# sensor.net
KiCad netlist of a schematic drawn in Altium Designer
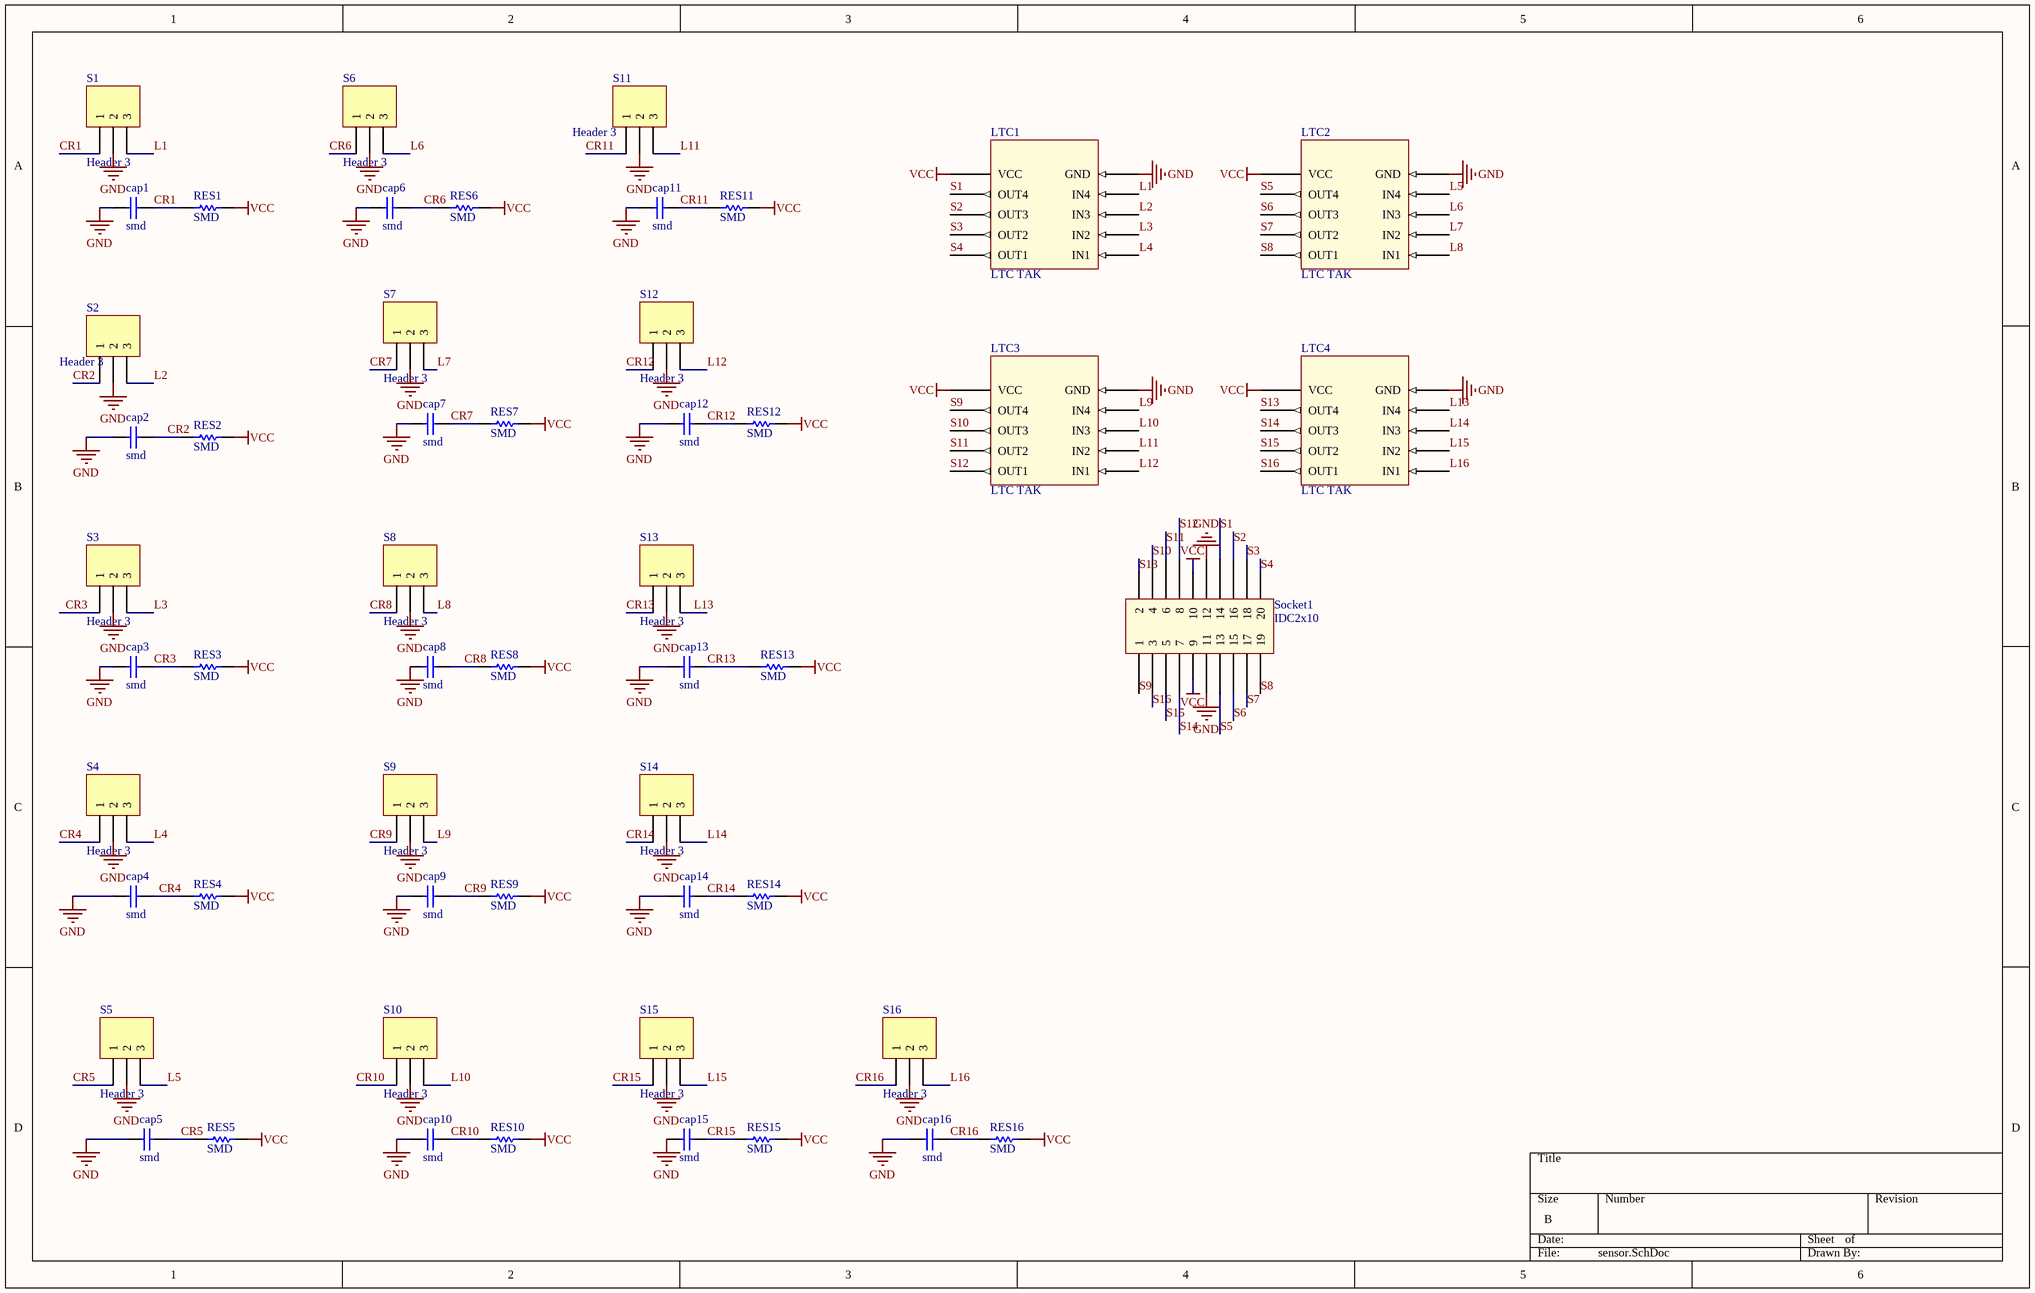
[diagram p0: sensor.SchDoc]

(export (version "E")
  (design (tool "Eeschema 10.0.6"))
  (components
    (comp (ref "cap1") (value "smd") (footprint "Cap SMD") (libsource (lib "Farzanegan") (part "Cap SMD")))
    (comp (ref "cap2") (value "smd") (footprint "Cap SMD") (libsource (lib "Farzanegan") (part "Cap SMD")))
    (comp (ref "cap3") (value "smd") (footprint "Cap SMD") (libsource (lib "Farzanegan") (part "Cap SMD")))
    (comp (ref "cap4") (value "smd") (footprint "Cap SMD") (libsource (lib "Farzanegan") (part "Cap SMD")))
    (comp (ref "cap5") (value "smd") (footprint "Cap SMD") (libsource (lib "Farzanegan") (part "Cap SMD")))
    (comp (ref "cap6") (value "smd") (footprint "Cap SMD") (libsource (lib "Farzanegan") (part "Cap SMD")))
    (comp (ref "cap7") (value "smd") (footprint "Cap SMD") (libsource (lib "Farzanegan") (part "Cap SMD")))
    (comp (ref "cap8") (value "smd") (footprint "Cap SMD") (libsource (lib "Farzanegan") (part "Cap SMD")))
    (comp (ref "cap9") (value "smd") (footprint "Cap SMD") (libsource (lib "Farzanegan") (part "Cap SMD")))
    (comp (ref "cap10") (value "smd") (footprint "Cap SMD") (libsource (lib "Farzanegan") (part "Cap SMD")))
    (comp (ref "cap11") (value "smd") (footprint "Cap SMD") (libsource (lib "Farzanegan") (part "Cap SMD")))
    (comp (ref "cap12") (value "smd") (footprint "Cap SMD") (libsource (lib "Farzanegan") (part "Cap SMD")))
    (comp (ref "cap13") (value "smd") (footprint "Cap SMD") (libsource (lib "Farzanegan") (part "Cap SMD")))
    (comp (ref "cap14") (value "smd") (footprint "Cap SMD") (libsource (lib "Farzanegan") (part "Cap SMD")))
    (comp (ref "cap15") (value "smd") (footprint "Cap SMD") (libsource (lib "Farzanegan") (part "Cap SMD")))
    (comp (ref "cap16") (value "smd") (footprint "Cap SMD") (libsource (lib "Farzanegan") (part "Cap SMD")))
    (comp (ref "LTC1")
      (value "LTC TAK")
      (footprint "LTC TAK")
      (libsource (lib "Farzanegan") (part "LTC TAK"))
    )
    (comp (ref "LTC2")
      (value "LTC TAK")
      (footprint "LTC TAK")
      (libsource (lib "Farzanegan") (part "LTC TAK"))
    )
    (comp (ref "LTC3")
      (value "LTC TAK")
      (footprint "LTC TAK")
      (libsource (lib "Farzanegan") (part "LTC TAK"))
    )
    (comp (ref "LTC4")
      (value "LTC TAK")
      (footprint "LTC TAK")
      (libsource (lib "Farzanegan") (part "LTC TAK"))
    )
    (comp (ref "RES1")
      (value "SMD")
      (footprint "Resistor SMD 1206")
      (libsource (lib "Farzanegan") (part "Res SMD"))
    )
    (comp (ref "RES2")
      (value "SMD")
      (footprint "Resistor SMD 1206")
      (libsource (lib "Farzanegan") (part "Res SMD"))
    )
    (comp (ref "RES3")
      (value "SMD")
      (footprint "Resistor SMD 1206")
      (libsource (lib "Farzanegan") (part "Res SMD"))
    )
    (comp (ref "RES4")
      (value "SMD")
      (footprint "Resistor SMD 1206")
      (libsource (lib "Farzanegan") (part "Res SMD"))
    )
    (comp (ref "RES5")
      (value "SMD")
      (footprint "Resistor SMD 1206")
      (libsource (lib "Farzanegan") (part "Res SMD"))
    )
    (comp (ref "RES6")
      (value "SMD")
      (footprint "Resistor SMD 1206")
      (libsource (lib "Farzanegan") (part "Res SMD"))
    )
    (comp (ref "RES7")
      (value "SMD")
      (footprint "Resistor SMD 1206")
      (libsource (lib "Farzanegan") (part "Res SMD"))
    )
    (comp (ref "RES8")
      (value "SMD")
      (footprint "Resistor SMD 1206")
      (libsource (lib "Farzanegan") (part "Res SMD"))
    )
    (comp (ref "RES9")
      (value "SMD")
      (footprint "Resistor SMD 1206")
      (libsource (lib "Farzanegan") (part "Res SMD"))
    )
    (comp (ref "RES10")
      (value "SMD")
      (footprint "Resistor SMD 1206")
      (libsource (lib "Farzanegan") (part "Res SMD"))
    )
    (comp (ref "RES11")
      (value "SMD")
      (footprint "Resistor SMD 1206")
      (libsource (lib "Farzanegan") (part "Res SMD"))
    )
    (comp (ref "RES12")
      (value "SMD")
      (footprint "Resistor SMD 1206")
      (libsource (lib "Farzanegan") (part "Res SMD"))
    )
    (comp (ref "RES13")
      (value "SMD")
      (footprint "Resistor SMD 1206")
      (libsource (lib "Farzanegan") (part "Res SMD"))
    )
    (comp (ref "RES14")
      (value "SMD")
      (footprint "Resistor SMD 1206")
      (libsource (lib "Farzanegan") (part "Res SMD"))
    )
    (comp (ref "RES15")
      (value "SMD")
      (footprint "Resistor SMD 1206")
      (libsource (lib "Farzanegan") (part "Res SMD"))
    )
    (comp (ref "RES16")
      (value "SMD")
      (footprint "Resistor SMD 1206")
      (libsource (lib "Farzanegan") (part "Res SMD"))
    )
    (comp (ref "S1")
      (value "Header 3")
      (footprint "HDR1X3")
      (description "Header, 3-Pin")
      (fields (field (name "PUBLISHER") "Altium Limited"))
      (libsource (lib "Miscellaneous Connectors") (part "Header 3"))
    )
    (comp (ref "S2")
      (value "Header 3")
      (footprint "HDR1X3")
      (description "Header, 3-Pin")
      (fields (field (name "PUBLISHER") "Altium Limited"))
      (libsource (lib "Miscellaneous Connectors") (part "Header 3"))
    )
    (comp (ref "S3")
      (value "Header 3")
      (footprint "HDR1X3")
      (description "Header, 3-Pin")
      (fields (field (name "PUBLISHER") "Altium Limited"))
      (libsource (lib "Miscellaneous Connectors") (part "Header 3"))
    )
    (comp (ref "S4")
      (value "Header 3")
      (footprint "HDR1X3")
      (description "Header, 3-Pin")
      (fields (field (name "PUBLISHER") "Altium Limited"))
      (libsource (lib "Miscellaneous Connectors") (part "Header 3"))
    )
    (comp (ref "S5")
      (value "Header 3")
      (footprint "HDR1X3")
      (description "Header, 3-Pin")
      (fields (field (name "PUBLISHER") "Altium Limited"))
      (libsource (lib "Miscellaneous Connectors") (part "Header 3"))
    )
    (comp (ref "S6")
      (value "Header 3")
      (footprint "HDR1X3")
      (description "Header, 3-Pin")
      (fields (field (name "PUBLISHER") "Altium Limited"))
      (libsource (lib "Miscellaneous Connectors") (part "Header 3"))
    )
    (comp (ref "S7")
      (value "Header 3")
      (footprint "HDR1X3")
      (description "Header, 3-Pin")
      (fields (field (name "PUBLISHER") "Altium Limited"))
      (libsource (lib "Miscellaneous Connectors") (part "Header 3"))
    )
    (comp (ref "S8")
      (value "Header 3")
      (footprint "HDR1X3")
      (description "Header, 3-Pin")
      (fields (field (name "PUBLISHER") "Altium Limited"))
      (libsource (lib "Miscellaneous Connectors") (part "Header 3"))
    )
    (comp (ref "S9")
      (value "Header 3")
      (footprint "HDR1X3")
      (description "Header, 3-Pin")
      (fields (field (name "PUBLISHER") "Altium Limited"))
      (libsource (lib "Miscellaneous Connectors") (part "Header 3"))
    )
    (comp (ref "S10")
      (value "Header 3")
      (footprint "HDR1X3")
      (description "Header, 3-Pin")
      (fields (field (name "PUBLISHER") "Altium Limited"))
      (libsource (lib "Miscellaneous Connectors") (part "Header 3"))
    )
    (comp (ref "S11")
      (value "Header 3")
      (footprint "HDR1X3")
      (description "Header, 3-Pin")
      (fields (field (name "PUBLISHER") "Altium Limited"))
      (libsource (lib "Miscellaneous Connectors") (part "Header 3"))
    )
    (comp (ref "S12")
      (value "Header 3")
      (footprint "HDR1X3")
      (description "Header, 3-Pin")
      (fields (field (name "PUBLISHER") "Altium Limited"))
      (libsource (lib "Miscellaneous Connectors") (part "Header 3"))
    )
    (comp (ref "S13")
      (value "Header 3")
      (footprint "HDR1X3")
      (description "Header, 3-Pin")
      (fields (field (name "PUBLISHER") "Altium Limited"))
      (libsource (lib "Miscellaneous Connectors") (part "Header 3"))
    )
    (comp (ref "S14")
      (value "Header 3")
      (footprint "HDR1X3")
      (description "Header, 3-Pin")
      (fields (field (name "PUBLISHER") "Altium Limited"))
      (libsource (lib "Miscellaneous Connectors") (part "Header 3"))
    )
    (comp (ref "S15")
      (value "Header 3")
      (footprint "HDR1X3")
      (description "Header, 3-Pin")
      (fields (field (name "PUBLISHER") "Altium Limited"))
      (libsource (lib "Miscellaneous Connectors") (part "Header 3"))
    )
    (comp (ref "S16")
      (value "Header 3")
      (footprint "HDR1X3")
      (description "Header, 3-Pin")
      (fields (field (name "PUBLISHER") "Altium Limited"))
      (libsource (lib "Miscellaneous Connectors") (part "Header 3"))
    )
    (comp (ref "Socket1")
      (value "IDC2x10")
      (footprint "IDC 2x10")
      (libsource (lib "Farzanegan") (part "IDC 2x10"))
    )
  )
  (nets
    (net (code "1") (name "/CR1") (class "Default")
      (node (ref "RES1") (pin "1") (pinfunction "1_1") (pintype "passive"))
      (node (ref "S1") (pin "1") (pinfunction "1_1") (pintype "passive"))
      (node (ref "cap1") (pin "2") (pinfunction "2_2") (pintype "passive"))
    )
    (net (code "2") (name "/CR2") (class "Default")
      (node (ref "RES2") (pin "1") (pinfunction "1_1") (pintype "passive"))
      (node (ref "S2") (pin "1") (pinfunction "1_1") (pintype "passive"))
      (node (ref "cap2") (pin "2") (pinfunction "2_2") (pintype "passive"))
    )
    (net (code "3") (name "/CR3") (class "Default")
      (node (ref "RES3") (pin "1") (pinfunction "1_1") (pintype "passive"))
      (node (ref "S3") (pin "1") (pinfunction "1_1") (pintype "passive"))
      (node (ref "cap3") (pin "2") (pinfunction "2_2") (pintype "passive"))
    )
    (net (code "4") (name "/CR4") (class "Default")
      (node (ref "RES4") (pin "1") (pinfunction "1_1") (pintype "passive"))
      (node (ref "S4") (pin "1") (pinfunction "1_1") (pintype "passive"))
      (node (ref "cap4") (pin "2") (pinfunction "2_2") (pintype "passive"))
    )
    (net (code "5") (name "/CR5") (class "Default")
      (node (ref "RES5") (pin "1") (pinfunction "1_1") (pintype "passive"))
      (node (ref "S5") (pin "1") (pinfunction "1_1") (pintype "passive"))
      (node (ref "cap5") (pin "2") (pinfunction "2_2") (pintype "passive"))
    )
    (net (code "6") (name "/CR6") (class "Default")
      (node (ref "RES6") (pin "1") (pinfunction "1_1") (pintype "passive"))
      (node (ref "S6") (pin "1") (pinfunction "1_1") (pintype "passive"))
      (node (ref "cap6") (pin "2") (pinfunction "2_2") (pintype "passive"))
    )
    (net (code "7") (name "/CR7") (class "Default")
      (node (ref "RES7") (pin "1") (pinfunction "1_1") (pintype "passive"))
      (node (ref "S7") (pin "1") (pinfunction "1_1") (pintype "passive"))
      (node (ref "cap7") (pin "2") (pinfunction "2_2") (pintype "passive"))
    )
    (net (code "8") (name "/CR8") (class "Default")
      (node (ref "RES8") (pin "1") (pinfunction "1_1") (pintype "passive"))
      (node (ref "S8") (pin "1") (pinfunction "1_1") (pintype "passive"))
      (node (ref "cap8") (pin "2") (pinfunction "2_2") (pintype "passive"))
    )
    (net (code "9") (name "/CR9") (class "Default")
      (node (ref "RES9") (pin "1") (pinfunction "1_1") (pintype "passive"))
      (node (ref "S9") (pin "1") (pinfunction "1_1") (pintype "passive"))
      (node (ref "cap9") (pin "2") (pinfunction "2_2") (pintype "passive"))
    )
    (net (code "10") (name "/CR10") (class "Default")
      (node (ref "RES10") (pin "1") (pinfunction "1_1") (pintype "passive"))
      (node (ref "S10") (pin "1") (pinfunction "1_1") (pintype "passive"))
      (node (ref "cap10") (pin "2") (pinfunction "2_2") (pintype "passive"))
    )
    (net (code "11") (name "/CR11") (class "Default")
      (node (ref "RES11") (pin "1") (pinfunction "1_1") (pintype "passive"))
      (node (ref "S11") (pin "1") (pinfunction "1_1") (pintype "passive"))
      (node (ref "cap11") (pin "2") (pinfunction "2_2") (pintype "passive"))
    )
    (net (code "12") (name "/CR12") (class "Default")
      (node (ref "RES12") (pin "1") (pinfunction "1_1") (pintype "passive"))
      (node (ref "S12") (pin "1") (pinfunction "1_1") (pintype "passive"))
      (node (ref "cap12") (pin "2") (pinfunction "2_2") (pintype "passive"))
    )
    (net (code "13") (name "/CR13") (class "Default")
      (node (ref "RES13") (pin "1") (pinfunction "1_1") (pintype "passive"))
      (node (ref "S13") (pin "1") (pinfunction "1_1") (pintype "passive"))
      (node (ref "cap13") (pin "2") (pinfunction "2_2") (pintype "passive"))
    )
    (net (code "14") (name "/CR14") (class "Default")
      (node (ref "RES14") (pin "1") (pinfunction "1_1") (pintype "passive"))
      (node (ref "S14") (pin "1") (pinfunction "1_1") (pintype "passive"))
      (node (ref "cap14") (pin "2") (pinfunction "2_2") (pintype "passive"))
    )
    (net (code "15") (name "/CR15") (class "Default")
      (node (ref "RES15") (pin "1") (pinfunction "1_1") (pintype "passive"))
      (node (ref "S15") (pin "1") (pinfunction "1_1") (pintype "passive"))
      (node (ref "cap15") (pin "2") (pinfunction "2_2") (pintype "passive"))
    )
    (net (code "16") (name "/CR16") (class "Default")
      (node (ref "RES16") (pin "1") (pinfunction "1_1") (pintype "passive"))
      (node (ref "S16") (pin "1") (pinfunction "1_1") (pintype "passive"))
      (node (ref "cap16") (pin "2") (pinfunction "2_2") (pintype "passive"))
    )
    (net (code "17") (name "/L1") (class "Default")
      (node (ref "LTC1") (pin "9") (pinfunction "IN4_9") (pintype "input"))
      (node (ref "S1") (pin "3") (pinfunction "3_3") (pintype "passive"))
    )
    (net (code "18") (name "/L2") (class "Default")
      (node (ref "LTC1") (pin "8") (pinfunction "IN3_8") (pintype "input"))
      (node (ref "S2") (pin "3") (pinfunction "3_3") (pintype "passive"))
    )
    (net (code "19") (name "/L3") (class "Default")
      (node (ref "LTC1") (pin "7") (pinfunction "IN2_7") (pintype "input"))
      (node (ref "S3") (pin "3") (pinfunction "3_3") (pintype "passive"))
    )
    (net (code "20") (name "/L4") (class "Default")
      (node (ref "LTC1") (pin "6") (pinfunction "IN1_6") (pintype "input"))
      (node (ref "S4") (pin "3") (pinfunction "3_3") (pintype "passive"))
    )
    (net (code "21") (name "/L5") (class "Default")
      (node (ref "LTC2") (pin "9") (pinfunction "IN4_9") (pintype "input"))
      (node (ref "S5") (pin "3") (pinfunction "3_3") (pintype "passive"))
    )
    (net (code "22") (name "/L6") (class "Default")
      (node (ref "LTC2") (pin "8") (pinfunction "IN3_8") (pintype "input"))
      (node (ref "S6") (pin "3") (pinfunction "3_3") (pintype "passive"))
    )
    (net (code "23") (name "/L7") (class "Default")
      (node (ref "LTC2") (pin "7") (pinfunction "IN2_7") (pintype "input"))
      (node (ref "S7") (pin "3") (pinfunction "3_3") (pintype "passive"))
    )
    (net (code "24") (name "/L8") (class "Default")
      (node (ref "LTC2") (pin "6") (pinfunction "IN1_6") (pintype "input"))
      (node (ref "S8") (pin "3") (pinfunction "3_3") (pintype "passive"))
    )
    (net (code "25") (name "/L9") (class "Default")
      (node (ref "LTC3") (pin "9") (pinfunction "IN4_9") (pintype "input"))
      (node (ref "S9") (pin "3") (pinfunction "3_3") (pintype "passive"))
    )
    (net (code "26") (name "/L10") (class "Default")
      (node (ref "LTC3") (pin "8") (pinfunction "IN3_8") (pintype "input"))
      (node (ref "S10") (pin "3") (pinfunction "3_3") (pintype "passive"))
    )
    (net (code "27") (name "/L11") (class "Default")
      (node (ref "LTC3") (pin "7") (pinfunction "IN2_7") (pintype "input"))
      (node (ref "S11") (pin "3") (pinfunction "3_3") (pintype "passive"))
    )
    (net (code "28") (name "/L12") (class "Default")
      (node (ref "LTC3") (pin "6") (pinfunction "IN1_6") (pintype "input"))
      (node (ref "S12") (pin "3") (pinfunction "3_3") (pintype "passive"))
    )
    (net (code "29") (name "/L13") (class "Default")
      (node (ref "LTC4") (pin "9") (pinfunction "IN4_9") (pintype "input"))
      (node (ref "S13") (pin "3") (pinfunction "3_3") (pintype "passive"))
    )
    (net (code "30") (name "/L14") (class "Default")
      (node (ref "LTC4") (pin "8") (pinfunction "IN3_8") (pintype "input"))
      (node (ref "S14") (pin "3") (pinfunction "3_3") (pintype "passive"))
    )
    (net (code "31") (name "/L15") (class "Default")
      (node (ref "LTC4") (pin "7") (pinfunction "IN2_7") (pintype "input"))
      (node (ref "S15") (pin "3") (pinfunction "3_3") (pintype "passive"))
    )
    (net (code "32") (name "/L16") (class "Default")
      (node (ref "LTC4") (pin "6") (pinfunction "IN1_6") (pintype "input"))
      (node (ref "S16") (pin "3") (pinfunction "3_3") (pintype "passive"))
    )
    (net (code "33") (name "/S1") (class "Default")
      (node (ref "LTC1") (pin "2") (pinfunction "OUT4_2") (pintype "output"))
      (node (ref "Socket1") (pin "14") (pinfunction "14_14") (pintype "passive"))
    )
    (net (code "34") (name "/S2") (class "Default")
      (node (ref "LTC1") (pin "3") (pinfunction "OUT3_3") (pintype "output"))
      (node (ref "Socket1") (pin "16") (pinfunction "16_16") (pintype "passive"))
    )
    (net (code "35") (name "/S3") (class "Default")
      (node (ref "LTC1") (pin "4") (pinfunction "OUT2_4") (pintype "output"))
      (node (ref "Socket1") (pin "18") (pinfunction "18_18") (pintype "passive"))
    )
    (net (code "36") (name "/S4") (class "Default")
      (node (ref "LTC1") (pin "5") (pinfunction "OUT1_5") (pintype "output"))
      (node (ref "Socket1") (pin "20") (pinfunction "20_20") (pintype "passive"))
    )
    (net (code "37") (name "/S5") (class "Default")
      (node (ref "LTC2") (pin "2") (pinfunction "OUT4_2") (pintype "output"))
      (node (ref "Socket1") (pin "13") (pinfunction "13_13") (pintype "passive"))
    )
    (net (code "38") (name "/S6") (class "Default")
      (node (ref "LTC2") (pin "3") (pinfunction "OUT3_3") (pintype "output"))
      (node (ref "Socket1") (pin "15") (pinfunction "15_15") (pintype "passive"))
    )
    (net (code "39") (name "/S7") (class "Default")
      (node (ref "LTC2") (pin "4") (pinfunction "OUT2_4") (pintype "output"))
      (node (ref "Socket1") (pin "17") (pinfunction "17_17") (pintype "passive"))
    )
    (net (code "40") (name "/S8") (class "Default")
      (node (ref "LTC2") (pin "5") (pinfunction "OUT1_5") (pintype "output"))
      (node (ref "Socket1") (pin "19") (pinfunction "19_19") (pintype "passive"))
    )
    (net (code "41") (name "/S9") (class "Default")
      (node (ref "LTC3") (pin "2") (pinfunction "OUT4_2") (pintype "output"))
      (node (ref "Socket1") (pin "1") (pinfunction "1_1") (pintype "passive"))
    )
    (net (code "42") (name "/S10") (class "Default")
      (node (ref "LTC3") (pin "3") (pinfunction "OUT3_3") (pintype "output"))
      (node (ref "Socket1") (pin "4") (pinfunction "4_4") (pintype "passive"))
    )
    (net (code "43") (name "/S11") (class "Default")
      (node (ref "LTC3") (pin "4") (pinfunction "OUT2_4") (pintype "output"))
      (node (ref "Socket1") (pin "6") (pinfunction "6_6") (pintype "passive"))
    )
    (net (code "44") (name "/S12") (class "Default")
      (node (ref "LTC3") (pin "5") (pinfunction "OUT1_5") (pintype "output"))
      (node (ref "Socket1") (pin "8") (pinfunction "8_8") (pintype "passive"))
    )
    (net (code "45") (name "/S13") (class "Default")
      (node (ref "LTC4") (pin "2") (pinfunction "OUT4_2") (pintype "output"))
      (node (ref "Socket1") (pin "2") (pinfunction "2_2") (pintype "passive"))
    )
    (net (code "46") (name "/S14") (class "Default")
      (node (ref "LTC4") (pin "3") (pinfunction "OUT3_3") (pintype "output"))
      (node (ref "Socket1") (pin "7") (pinfunction "7_7") (pintype "passive"))
    )
    (net (code "47") (name "/S15") (class "Default")
      (node (ref "LTC4") (pin "4") (pinfunction "OUT2_4") (pintype "output"))
      (node (ref "Socket1") (pin "5") (pinfunction "5_5") (pintype "passive"))
    )
    (net (code "48") (name "/S16") (class "Default")
      (node (ref "LTC4") (pin "5") (pinfunction "OUT1_5") (pintype "output"))
      (node (ref "Socket1") (pin "3") (pinfunction "3_3") (pintype "passive"))
    )
    (net (code "49") (name "GND") (class "Default")
      (node (ref "LTC1") (pin "10") (pinfunction "GND_10") (pintype "input"))
      (node (ref "LTC2") (pin "10") (pinfunction "GND_10") (pintype "input"))
      (node (ref "LTC3") (pin "10") (pinfunction "GND_10") (pintype "input"))
      (node (ref "LTC4") (pin "10") (pinfunction "GND_10") (pintype "input"))
      (node (ref "S1") (pin "2") (pinfunction "2_2") (pintype "passive"))
      (node (ref "S10") (pin "2") (pinfunction "2_2") (pintype "passive"))
      (node (ref "S11") (pin "2") (pinfunction "2_2") (pintype "passive"))
      (node (ref "S12") (pin "2") (pinfunction "2_2") (pintype "passive"))
      (node (ref "S13") (pin "2") (pinfunction "2_2") (pintype "passive"))
      (node (ref "S14") (pin "2") (pinfunction "2_2") (pintype "passive"))
      (node (ref "S15") (pin "2") (pinfunction "2_2") (pintype "passive"))
      (node (ref "S16") (pin "2") (pinfunction "2_2") (pintype "passive"))
      (node (ref "S2") (pin "2") (pinfunction "2_2") (pintype "passive"))
      (node (ref "S3") (pin "2") (pinfunction "2_2") (pintype "passive"))
      (node (ref "S4") (pin "2") (pinfunction "2_2") (pintype "passive"))
      (node (ref "S5") (pin "2") (pinfunction "2_2") (pintype "passive"))
      (node (ref "S6") (pin "2") (pinfunction "2_2") (pintype "passive"))
      (node (ref "S7") (pin "2") (pinfunction "2_2") (pintype "passive"))
      (node (ref "S8") (pin "2") (pinfunction "2_2") (pintype "passive"))
      (node (ref "S9") (pin "2") (pinfunction "2_2") (pintype "passive"))
      (node (ref "Socket1") (pin "11") (pinfunction "11_11") (pintype "passive"))
      (node (ref "Socket1") (pin "12") (pinfunction "12_12") (pintype "passive"))
      (node (ref "cap1") (pin "1") (pinfunction "1_1") (pintype "passive"))
      (node (ref "cap10") (pin "1") (pinfunction "1_1") (pintype "passive"))
      (node (ref "cap11") (pin "1") (pinfunction "1_1") (pintype "passive"))
      (node (ref "cap12") (pin "1") (pinfunction "1_1") (pintype "passive"))
      (node (ref "cap13") (pin "1") (pinfunction "1_1") (pintype "passive"))
      (node (ref "cap14") (pin "1") (pinfunction "1_1") (pintype "passive"))
      (node (ref "cap15") (pin "1") (pinfunction "1_1") (pintype "passive"))
      (node (ref "cap16") (pin "1") (pinfunction "1_1") (pintype "passive"))
      (node (ref "cap2") (pin "1") (pinfunction "1_1") (pintype "passive"))
      (node (ref "cap3") (pin "1") (pinfunction "1_1") (pintype "passive"))
      (node (ref "cap4") (pin "1") (pinfunction "1_1") (pintype "passive"))
      (node (ref "cap5") (pin "1") (pinfunction "1_1") (pintype "passive"))
      (node (ref "cap6") (pin "1") (pinfunction "1_1") (pintype "passive"))
      (node (ref "cap7") (pin "1") (pinfunction "1_1") (pintype "passive"))
      (node (ref "cap8") (pin "1") (pinfunction "1_1") (pintype "passive"))
      (node (ref "cap9") (pin "1") (pinfunction "1_1") (pintype "passive"))
    )
    (net (code "50") (name "VCC") (class "Default")
      (node (ref "LTC1") (pin "1") (pinfunction "VCC_1") (pintype "power_in"))
      (node (ref "LTC2") (pin "1") (pinfunction "VCC_1") (pintype "power_in"))
      (node (ref "LTC3") (pin "1") (pinfunction "VCC_1") (pintype "power_in"))
      (node (ref "LTC4") (pin "1") (pinfunction "VCC_1") (pintype "power_in"))
      (node (ref "RES1") (pin "2") (pinfunction "2_2") (pintype "passive"))
      (node (ref "RES10") (pin "2") (pinfunction "2_2") (pintype "passive"))
      (node (ref "RES11") (pin "2") (pinfunction "2_2") (pintype "passive"))
      (node (ref "RES12") (pin "2") (pinfunction "2_2") (pintype "passive"))
      (node (ref "RES13") (pin "2") (pinfunction "2_2") (pintype "passive"))
      (node (ref "RES14") (pin "2") (pinfunction "2_2") (pintype "passive"))
      (node (ref "RES15") (pin "2") (pinfunction "2_2") (pintype "passive"))
      (node (ref "RES16") (pin "2") (pinfunction "2_2") (pintype "passive"))
      (node (ref "RES2") (pin "2") (pinfunction "2_2") (pintype "passive"))
      (node (ref "RES3") (pin "2") (pinfunction "2_2") (pintype "passive"))
      (node (ref "RES4") (pin "2") (pinfunction "2_2") (pintype "passive"))
      (node (ref "RES5") (pin "2") (pinfunction "2_2") (pintype "passive"))
      (node (ref "RES6") (pin "2") (pinfunction "2_2") (pintype "passive"))
      (node (ref "RES7") (pin "2") (pinfunction "2_2") (pintype "passive"))
      (node (ref "RES8") (pin "2") (pinfunction "2_2") (pintype "passive"))
      (node (ref "RES9") (pin "2") (pinfunction "2_2") (pintype "passive"))
      (node (ref "Socket1") (pin "10") (pinfunction "10_10") (pintype "passive"))
      (node (ref "Socket1") (pin "9") (pinfunction "9_9") (pintype "passive"))
    )
  )
)
